# norbi_lm_pl_dcr_power_ch.net
KiCad netlist of a schematic drawn in Altium Designer
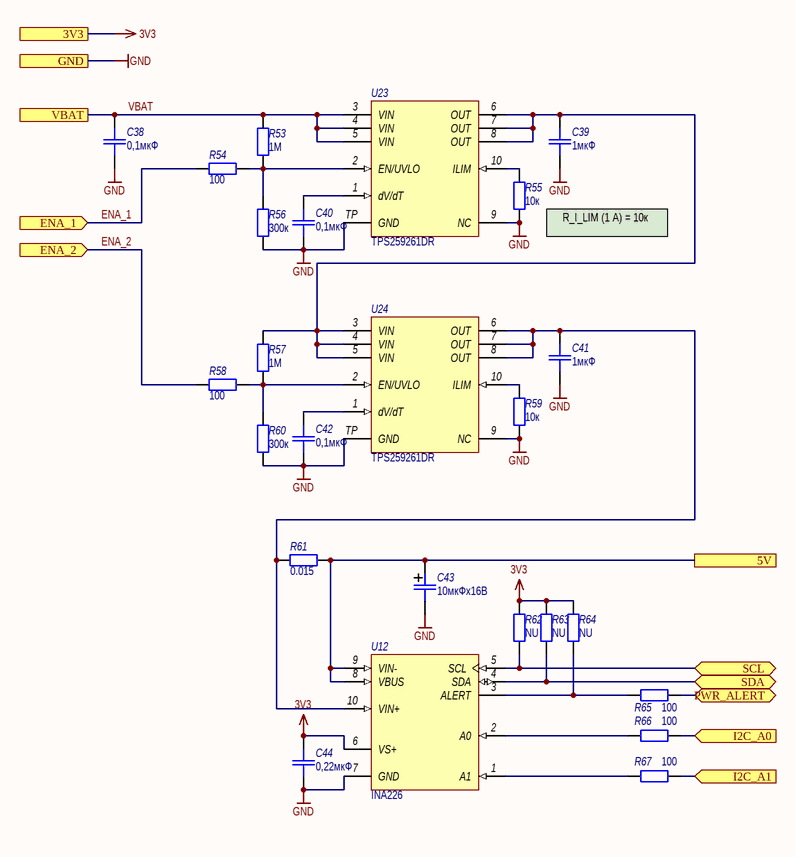
[diagram p0: norbi_lm_pl_dcr_power_ch.SchDoc]

(export (version "E")
  (design (tool "Eeschema 10.0.6"))
  (components
    (comp (ref "C38")
      (value "0,1мкФ")
      (footprint "CR-0603")
      (description "Конденсатор для поверхностного монтажа")
      (libsource (lib "my_passive") (part "C_smd"))
    )
    (comp (ref "C39")
      (value "1мкФ")
      (footprint "CR-0603")
      (description "Конденсатор для поверхностного монтажа")
      (libsource (lib "my_passive") (part "C_smd"))
    )
    (comp (ref "C40")
      (value "0,1мкФ")
      (footprint "CR-0603")
      (description "Конденсатор для поверхностного монтажа")
      (libsource (lib "my_passive") (part "C_smd"))
    )
    (comp (ref "C41")
      (value "1мкФ")
      (footprint "CR-0603")
      (description "Конденсатор для поверхностного монтажа")
      (libsource (lib "my_passive") (part "C_smd"))
    )
    (comp (ref "C42")
      (value "0,1мкФ")
      (footprint "CR-0603")
      (description "Конденсатор для поверхностного монтажа")
      (libsource (lib "my_passive") (part "C_smd"))
    )
    (comp (ref "C43")
      (value "10мкФх16В")
      (footprint "C_SMD_SIZE_B")
      (description "Поляризованный конеднсатор для поверхностного монтажа")
      (libsource (lib "my_passive") (part "C_pol_smd"))
    )
    (comp (ref "C44")
      (value "0,22мкФ")
      (footprint "CR-0603")
      (description "Конденсатор для поверхностного монтажа")
      (libsource (lib "my_passive") (part "C_smd"))
    )
    (comp (ref "R53")
      (value "1М")
      (footprint "CR-0603")
      (description "Резистор для поверхностного монтажа")
      (libsource (lib "my_passive") (part "R_smd"))
    )
    (comp (ref "R54")
      (value "100")
      (footprint "CR-0603")
      (description "Резистор для поверхностного монтажа")
      (libsource (lib "") (part "R_smd_1"))
    )
    (comp (ref "R55")
      (value "10к")
      (footprint "CR-0603")
      (description "Резистор для поверхностного монтажа")
      (libsource (lib "my_passive") (part "R_smd"))
    )
    (comp (ref "R56")
      (value "300к")
      (footprint "CR-0603")
      (description "Резистор для поверхностного монтажа")
      (libsource (lib "my_passive") (part "R_smd"))
    )
    (comp (ref "R57")
      (value "1М")
      (footprint "CR-0603")
      (description "Резистор для поверхностного монтажа")
      (libsource (lib "my_passive") (part "R_smd"))
    )
    (comp (ref "R58")
      (value "100")
      (footprint "CR-0603")
      (description "Резистор для поверхностного монтажа")
      (libsource (lib "") (part "R_smd_1"))
    )
    (comp (ref "R59")
      (value "10к")
      (footprint "CR-0603")
      (description "Резистор для поверхностного монтажа")
      (libsource (lib "my_passive") (part "R_smd"))
    )
    (comp (ref "R60")
      (value "300к")
      (footprint "CR-0603")
      (description "Резистор для поверхностного монтажа")
      (libsource (lib "my_passive") (part "R_smd"))
    )
    (comp (ref "R61")
      (value "0.015")
      (footprint "CR-1206")
      (description "Резистор для поверхностного монтажа")
      (libsource (lib "") (part "R_smd_1"))
    )
    (comp (ref "R62")
      (value "NU")
      (footprint "CR-0603")
      (description "Резистор для поверхностного монтажа")
      (libsource (lib "my_passive") (part "R_smd"))
    )
    (comp (ref "R63")
      (value "NU")
      (footprint "CR-0603")
      (description "Резистор для поверхностного монтажа")
      (libsource (lib "my_passive") (part "R_smd"))
    )
    (comp (ref "R64")
      (value "NU")
      (footprint "CR-0603")
      (description "Резистор для поверхностного монтажа")
      (libsource (lib "my_passive") (part "R_smd"))
    )
    (comp (ref "R65")
      (value "100")
      (footprint "CR-0603")
      (description "Резистор для поверхностного монтажа")
      (libsource (lib "") (part "R_smd_1"))
    )
    (comp (ref "R66")
      (value "100")
      (footprint "CR-0603")
      (description "Резистор для поверхностного монтажа")
      (libsource (lib "") (part "R_smd_1"))
    )
    (comp (ref "R67")
      (value "100")
      (footprint "CR-0603")
      (description "Резистор для поверхностного монтажа")
      (libsource (lib "") (part "R_smd_1"))
    )
    (comp (ref "U12")
      (value "INA261")
      (footprint "VSSOP-8")
      (description "High- or Low-Side Measurement, Bidirectional Current and Power Monitor With I2C Interface")
      (fields (field (name "НАИМЕНОВАНИЕ") "INA226"))
      (libsource (lib "my_power") (part "INA226"))
    )
    (comp (ref "U23")
      (value "TPS259261ВК")
      (footprint "VSON-10")
      (description "Simple 5-V/12-V eFuse Protection Switches")
      (fields (field (name "НАИМЕНОВАНИЕ") "TPS259261DR"))
      (libsource (lib "my_power") (part "TPS259261"))
    )
    (comp (ref "U24")
      (value "TPS259261ВК")
      (footprint "VSON-10")
      (description "Simple 5-V/12-V eFuse Protection Switches")
      (fields (field (name "НАИМЕНОВАНИЕ") "TPS259261DR"))
      (libsource (lib "my_power") (part "TPS259261"))
    )
  )
  (nets
    (net (code "1") (name "/5V") (class "Default")
      (node (ref "C43") (pin "1") (pinfunction "1_1") (pintype "passive"))
      (node (ref "R61") (pin "1") (pinfunction "1_1") (pintype "passive"))
      (node (ref "U12") (pin "8") (pinfunction "VBUS_8") (pintype "input"))
      (node (ref "U12") (pin "9") (pinfunction "VIN-_9") (pintype "input"))
    )
    (net (code "2") (name "/ENA_1") (class "Default")
      (node (ref "R54") (pin "2") (pinfunction "2_2") (pintype "passive"))
    )
    (net (code "3") (name "/ENA_2") (class "Default")
      (node (ref "R58") (pin "2") (pinfunction "2_2") (pintype "passive"))
    )
    (net (code "4") (name "/I2C_A0") (class "Default")
      (node (ref "R66") (pin "1") (pinfunction "1_1") (pintype "passive"))
    )
    (net (code "5") (name "/I2C_A1") (class "Default")
      (node (ref "R67") (pin "1") (pinfunction "1_1") (pintype "passive"))
    )
    (net (code "6") (name "/PWR_ALERT") (class "Default")
      (node (ref "R65") (pin "1") (pinfunction "1_1") (pintype "passive"))
    )
    (net (code "7") (name "/SCL") (class "Default")
      (node (ref "R62") (pin "1") (pinfunction "1_1") (pintype "passive"))
      (node (ref "U12") (pin "5") (pinfunction "SCL_5") (pintype "input"))
    )
    (net (code "8") (name "/SDA") (class "Default")
      (node (ref "R63") (pin "1") (pinfunction "1_1") (pintype "passive"))
      (node (ref "U12") (pin "4") (pinfunction "SDA_4") (pintype "bidirectional"))
    )
    (net (code "9") (name "/VBAT") (class "Default")
      (node (ref "C38") (pin "2") (pinfunction "2_2") (pintype "passive"))
      (node (ref "R53") (pin "2") (pinfunction "2_2") (pintype "passive"))
      (node (ref "U23") (pin "3") (pinfunction "VIN_3") (pintype "power_in"))
      (node (ref "U23") (pin "4") (pinfunction "VIN_4") (pintype "power_in"))
      (node (ref "U23") (pin "5") (pinfunction "VIN_5") (pintype "power_in"))
    )
    (net (code "10") (name "3V3") (class "Default")
      (node (ref "C44") (pin "2") (pinfunction "2_2") (pintype "passive"))
      (node (ref "R62") (pin "2") (pinfunction "2_2") (pintype "passive"))
      (node (ref "R63") (pin "2") (pinfunction "2_2") (pintype "passive"))
      (node (ref "R64") (pin "2") (pinfunction "2_2") (pintype "passive"))
      (node (ref "U12") (pin "6") (pinfunction "VS+_6") (pintype "power_in"))
    )
    (net (code "11") (name "GND") (class "Default")
      (node (ref "C38") (pin "1") (pinfunction "1_1") (pintype "passive"))
      (node (ref "C39") (pin "1") (pinfunction "1_1") (pintype "passive"))
      (node (ref "C40") (pin "1") (pinfunction "1_1") (pintype "passive"))
      (node (ref "C41") (pin "1") (pinfunction "1_1") (pintype "passive"))
      (node (ref "C42") (pin "1") (pinfunction "1_1") (pintype "passive"))
      (node (ref "C43") (pin "2") (pinfunction "2_2") (pintype "passive"))
      (node (ref "C44") (pin "1") (pinfunction "1_1") (pintype "passive"))
      (node (ref "R55") (pin "1") (pinfunction "1_1") (pintype "passive"))
      (node (ref "R56") (pin "1") (pinfunction "1_1") (pintype "passive"))
      (node (ref "R59") (pin "1") (pinfunction "1_1") (pintype "passive"))
      (node (ref "R60") (pin "1") (pinfunction "1_1") (pintype "passive"))
      (node (ref "U12") (pin "7") (pinfunction "GND_7") (pintype "power_in"))
      (node (ref "U23") (pin "9") (pinfunction "NC_9") (pintype "passive"))
      (node (ref "U23") (pin "TP") (pinfunction "GND_TP") (pintype "power_in"))
      (node (ref "U24") (pin "9") (pinfunction "NC_9") (pintype "passive"))
      (node (ref "U24") (pin "TP") (pinfunction "GND_TP") (pintype "power_in"))
    )
    (net (code "12") (name "Net-(C39-Pad2)") (class "Default")
      (node (ref "C39") (pin "2") (pinfunction "2_2") (pintype "passive"))
      (node (ref "R57") (pin "2") (pinfunction "2_2") (pintype "passive"))
      (node (ref "U23") (pin "6") (pinfunction "OUT_6") (pintype "power_in"))
      (node (ref "U23") (pin "7") (pinfunction "OUT_7") (pintype "power_in"))
      (node (ref "U23") (pin "8") (pinfunction "OUT_8") (pintype "power_in"))
      (node (ref "U24") (pin "3") (pinfunction "VIN_3") (pintype "power_in"))
      (node (ref "U24") (pin "4") (pinfunction "VIN_4") (pintype "power_in"))
      (node (ref "U24") (pin "5") (pinfunction "VIN_5") (pintype "power_in"))
    )
    (net (code "13") (name "Net-(U12-A0)") (class "Default")
      (node (ref "R66") (pin "2") (pinfunction "2_2") (pintype "passive"))
      (node (ref "U12") (pin "2") (pinfunction "A0_2") (pintype "input"))
    )
    (net (code "14") (name "Net-(U12-A1)") (class "Default")
      (node (ref "R67") (pin "2") (pinfunction "2_2") (pintype "passive"))
      (node (ref "U12") (pin "1") (pinfunction "A1_1") (pintype "input"))
    )
    (net (code "15") (name "Net-(U12-ALERT)") (class "Default")
      (node (ref "R64") (pin "1") (pinfunction "1_1") (pintype "passive"))
      (node (ref "R65") (pin "2") (pinfunction "2_2") (pintype "passive"))
      (node (ref "U12") (pin "3") (pinfunction "ALERT_3") (pintype "open_collector"))
    )
    (net (code "16") (name "Net-(U12-VIN+)") (class "Default")
      (node (ref "C41") (pin "2") (pinfunction "2_2") (pintype "passive"))
      (node (ref "R61") (pin "2") (pinfunction "2_2") (pintype "passive"))
      (node (ref "U12") (pin "10") (pinfunction "VIN+_10") (pintype "input"))
      (node (ref "U24") (pin "6") (pinfunction "OUT_6") (pintype "power_in"))
      (node (ref "U24") (pin "7") (pinfunction "OUT_7") (pintype "power_in"))
      (node (ref "U24") (pin "8") (pinfunction "OUT_8") (pintype "power_in"))
    )
    (net (code "17") (name "Net-(U23-EN{slash}UVLO)") (class "Default")
      (node (ref "R53") (pin "1") (pinfunction "1_1") (pintype "passive"))
      (node (ref "R54") (pin "1") (pinfunction "1_1") (pintype "passive"))
      (node (ref "R56") (pin "2") (pinfunction "2_2") (pintype "passive"))
      (node (ref "U23") (pin "2") (pinfunction "EN/UVLO_2") (pintype "input"))
    )
    (net (code "18") (name "Net-(U23-ILIM)") (class "Default")
      (node (ref "R55") (pin "2") (pinfunction "2_2") (pintype "passive"))
      (node (ref "U23") (pin "10") (pinfunction "ILIM_10") (pintype "input"))
    )
    (net (code "19") (name "Net-(U23-dV{slash}dT)") (class "Default")
      (node (ref "C40") (pin "2") (pinfunction "2_2") (pintype "passive"))
      (node (ref "U23") (pin "1") (pinfunction "dV/dT_1") (pintype "input"))
    )
    (net (code "20") (name "Net-(U24-EN{slash}UVLO)") (class "Default")
      (node (ref "R57") (pin "1") (pinfunction "1_1") (pintype "passive"))
      (node (ref "R58") (pin "1") (pinfunction "1_1") (pintype "passive"))
      (node (ref "R60") (pin "2") (pinfunction "2_2") (pintype "passive"))
      (node (ref "U24") (pin "2") (pinfunction "EN/UVLO_2") (pintype "input"))
    )
    (net (code "21") (name "Net-(U24-ILIM)") (class "Default")
      (node (ref "R59") (pin "2") (pinfunction "2_2") (pintype "passive"))
      (node (ref "U24") (pin "10") (pinfunction "ILIM_10") (pintype "input"))
    )
    (net (code "22") (name "Net-(U24-dV{slash}dT)") (class "Default")
      (node (ref "C42") (pin "2") (pinfunction "2_2") (pintype "passive"))
      (node (ref "U24") (pin "1") (pinfunction "dV/dT_1") (pintype "input"))
    )
  )
)
